# analogTCO-RJ-alone.net
KiCad netlist of a schematic drawn in EAGLE
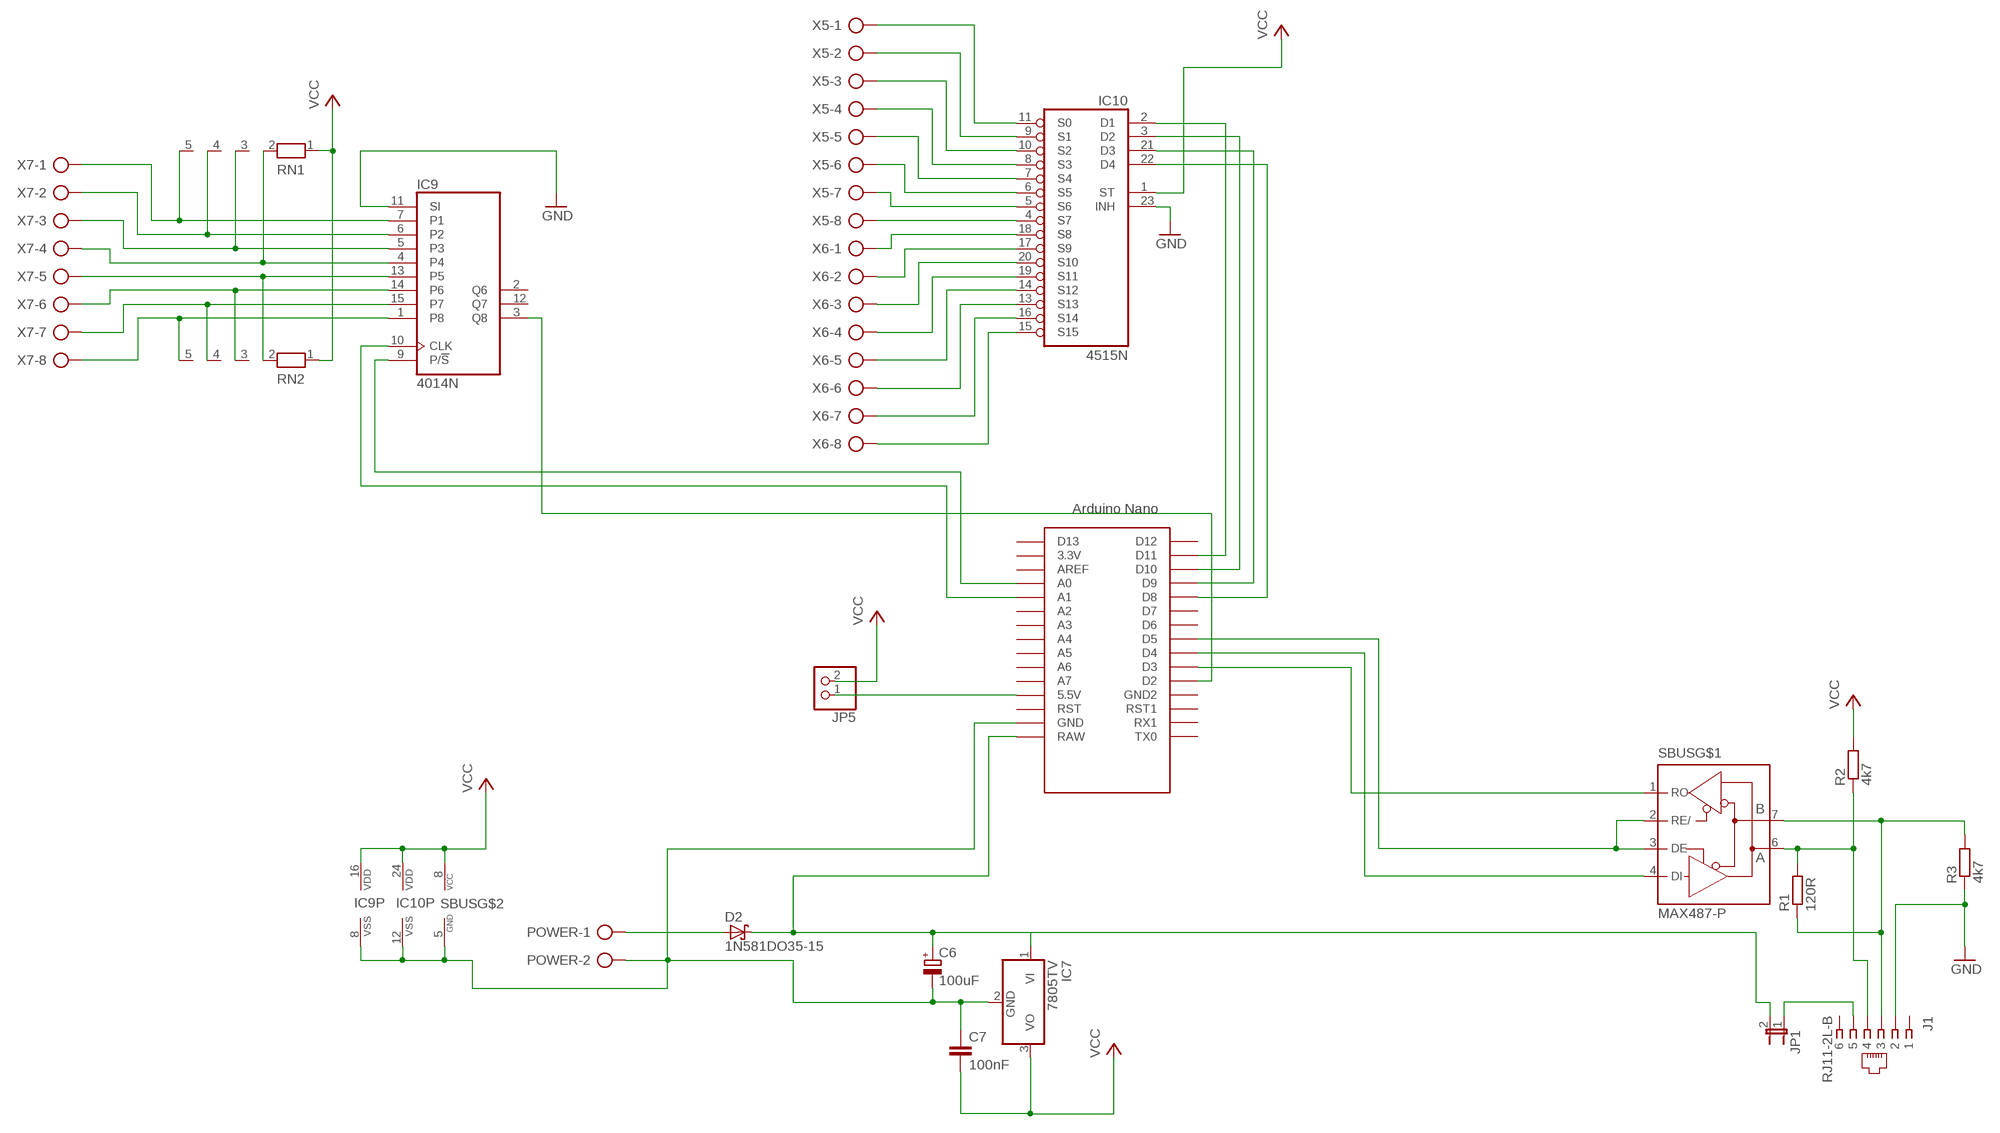
[diagram p0: schematic, sheet 1]

(export (version "E")
  (design (tool "Eeschema 10.0.6"))
  (components
    (comp (ref "C6")
      (value "100uF")
      (footprint "eagle-import:E2,5-6")
      (libsource (lib "eagle-import") (part "CPOL-EUE2.5-6"))
    )
    (comp (ref "C7")
      (value "100nF")
      (footprint "eagle-import:C025-025X050")
      (libsource (lib "eagle-import") (part "C-EU025-025X050"))
    )
    (comp (ref "D2")
      (value "1N581DO35-15")
      (footprint "eagle-import:DO35-10")
      (libsource (lib "eagle-import") (part "1N581DO35-15"))
    )
    (comp (ref "IC7")
      (value "7805TV")
      (footprint "eagle-import:TO220V")
      (libsource (lib "eagle-import") (part "78TV05"))
    )
    (comp (ref "IC9")
      (value "4014N")
      (footprint "eagle-import:DIL16")
      (libsource (lib "eagle-import") (part "4014N"))
    )
    (comp (ref "IC10")
      (value "4515N")
      (footprint "eagle-import:DIL24-6")
      (libsource (lib "eagle-import") (part "4515N"))
    )
    (comp (ref "J1")
      (value "RJ11-2L-B")
      (footprint "eagle-import:RJ11-NO_SHIELD")
      (fields (field (name "MF") "TYCO ELECTRONICS"))
      (libsource (lib "eagle-import") (part "RJ11-2L-B"))
    )
    (comp (ref "JP1")
      (value "JP1E")
      (footprint "eagle-import:JP1")
      (libsource (lib "eagle-import") (part "JP1E"))
    )
    (comp (ref "JP5")
      (value "PINHD-1X2")
      (footprint "eagle-import:1X02")
      (libsource (lib "eagle-import") (part "PINHD-1X2"))
    )
    (comp (ref "POWER")
      (value "AK500/2")
      (footprint "eagle-import:AK500_2")
      (libsource (lib "eagle-import") (part "AK500/2"))
    )
    (comp (ref "R1")
      (value "120R")
      (footprint "eagle-import:0207_12")
      (libsource (lib "eagle-import") (part "R-EU_0207/12"))
    )
    (comp (ref "R2")
      (value "4k7")
      (footprint "eagle-import:0207_12")
      (libsource (lib "eagle-import") (part "R-EU_0207/12"))
    )
    (comp (ref "R3")
      (value "4k7")
      (footprint "eagle-import:0207_12")
      (libsource (lib "eagle-import") (part "R-EU_0207/12"))
    )
    (comp (ref "RN1")
      (value "RN04")
      (footprint "eagle-import:RN-5")
      (libsource (lib "eagle-import") (part "RN04"))
    )
    (comp (ref "RN2")
      (value "RN04")
      (footprint "eagle-import:RN-5")
      (libsource (lib "eagle-import") (part "RN04"))
    )
    (comp (ref "SBUS")
      (value "MAX487-P")
      (footprint "eagle-import:DIL08")
      (libsource (lib "eagle-import") (part "MAX487-P"))
    )
    (comp (ref "U$1")
      (value "NANO")
      (footprint "eagle-import:NANO")
      (libsource (lib "eagle-import") (part "NANO"))
    )
    (comp (ref "X5")
      (value "AK500/8")
      (footprint "eagle-import:AK500_8")
      (libsource (lib "eagle-import") (part "AK500/8"))
    )
    (comp (ref "X6")
      (value "AK500/8")
      (footprint "eagle-import:AK500_8")
      (libsource (lib "eagle-import") (part "AK500/8"))
    )
    (comp (ref "X7")
      (value "AK500/8")
      (footprint "eagle-import:AK500_8")
      (libsource (lib "eagle-import") (part "AK500/8"))
    )
  )
  (nets
    (net (code "1") (name "GND") (class "Default")
      (node (ref "C6") (pin "-") (pinfunction "-_-") (pintype "passive"))
      (node (ref "C7") (pin "1") (pinfunction "1_1") (pintype "passive"))
      (node (ref "IC10") (pin "12") (pinfunction "VSS_12") (pintype "power_in"))
      (node (ref "IC10") (pin "23") (pinfunction "INH_23") (pintype "input"))
      (node (ref "IC7") (pin "2") (pinfunction "GND_2") (pintype "passive"))
      (node (ref "IC9") (pin "11") (pinfunction "SI_11") (pintype "input"))
      (node (ref "IC9") (pin "8") (pinfunction "VSS_8") (pintype "power_in"))
      (node (ref "J1") (pin "2") (pinfunction "2_2") (pintype "passive"))
      (node (ref "POWER") (pin "2") (pinfunction "KL_2") (pintype "passive"))
      (node (ref "R3") (pin "1") (pinfunction "1_1") (pintype "passive"))
      (node (ref "SBUS") (pin "5") (pinfunction "GND_5") (pintype "power_in"))
      (node (ref "U$1") (pin "GND") (pinfunction "GND_GND") (pintype "bidirectional"))
    )
    (net (code "2") (name "Net-(IC7-VI)") (class "Default")
      (node (ref "C6") (pin "+") (pinfunction "+_+") (pintype "passive"))
      (node (ref "D2") (pin "C") (pinfunction "C_C") (pintype "passive"))
      (node (ref "IC7") (pin "1") (pinfunction "VI_1") (pintype "input"))
      (node (ref "JP1") (pin "2") (pinfunction "2_2") (pintype "passive"))
      (node (ref "U$1") (pin "RAW") (pinfunction "RAW_RAW") (pintype "bidirectional"))
    )
    (net (code "3") (name "Net-(IC9A-CLK)") (class "Default")
      (node (ref "IC9") (pin "10") (pinfunction "CLK_10") (pintype "input"))
      (node (ref "U$1") (pin "A1") (pinfunction "A1_A1") (pintype "bidirectional"))
    )
    (net (code "4") (name "Net-(IC9A-P1)") (class "Default")
      (node (ref "IC9") (pin "7") (pinfunction "P1_7") (pintype "input"))
      (node (ref "RN1") (pin "5") (pinfunction "5_5") (pintype "passive"))
      (node (ref "X7") (pin "1") (pinfunction "KL_1") (pintype "passive"))
    )
    (net (code "5") (name "Net-(IC9A-P2)") (class "Default")
      (node (ref "IC9") (pin "6") (pinfunction "P2_6") (pintype "input"))
      (node (ref "RN1") (pin "4") (pinfunction "4_4") (pintype "passive"))
      (node (ref "X7") (pin "2") (pinfunction "KL_2") (pintype "passive"))
    )
    (net (code "6") (name "Net-(IC9A-P3)") (class "Default")
      (node (ref "IC9") (pin "5") (pinfunction "P3_5") (pintype "input"))
      (node (ref "RN1") (pin "3") (pinfunction "3_3") (pintype "passive"))
      (node (ref "X7") (pin "3") (pinfunction "KL_3") (pintype "passive"))
    )
    (net (code "7") (name "Net-(IC9A-P4)") (class "Default")
      (node (ref "IC9") (pin "4") (pinfunction "P4_4") (pintype "input"))
      (node (ref "RN1") (pin "2") (pinfunction "2_2") (pintype "passive"))
      (node (ref "X7") (pin "4") (pinfunction "KL_4") (pintype "passive"))
    )
    (net (code "8") (name "Net-(IC9A-P5)") (class "Default")
      (node (ref "IC9") (pin "13") (pinfunction "P5_13") (pintype "input"))
      (node (ref "RN2") (pin "2") (pinfunction "2_2") (pintype "passive"))
      (node (ref "X7") (pin "5") (pinfunction "KL_5") (pintype "passive"))
    )
    (net (code "9") (name "Net-(IC9A-P6)") (class "Default")
      (node (ref "IC9") (pin "14") (pinfunction "P6_14") (pintype "input"))
      (node (ref "RN2") (pin "3") (pinfunction "3_3") (pintype "passive"))
      (node (ref "X7") (pin "6") (pinfunction "KL_6") (pintype "passive"))
    )
    (net (code "10") (name "Net-(IC9A-P7)") (class "Default")
      (node (ref "IC9") (pin "15") (pinfunction "P7_15") (pintype "input"))
      (node (ref "RN2") (pin "4") (pinfunction "4_4") (pintype "passive"))
      (node (ref "X7") (pin "7") (pinfunction "KL_7") (pintype "passive"))
    )
    (net (code "11") (name "Net-(IC9A-P8)") (class "Default")
      (node (ref "IC9") (pin "1") (pinfunction "P8_1") (pintype "input"))
      (node (ref "RN2") (pin "5") (pinfunction "5_5") (pintype "passive"))
      (node (ref "X7") (pin "8") (pinfunction "KL_8") (pintype "passive"))
    )
    (net (code "12") (name "Net-(IC9A-P{slash}~{S})") (class "Default")
      (node (ref "IC9") (pin "9") (pinfunction "P/~{S}_9") (pintype "input"))
      (node (ref "U$1") (pin "A0") (pinfunction "A0_A0") (pintype "bidirectional"))
    )
    (net (code "13") (name "Net-(IC9A-Q8)") (class "Default")
      (node (ref "IC9") (pin "3") (pinfunction "Q8_3") (pintype "output"))
      (node (ref "U$1") (pin "D2") (pinfunction "D2_D2") (pintype "bidirectional"))
    )
    (net (code "14") (name "Net-(IC10A-D1)") (class "Default")
      (node (ref "IC10") (pin "2") (pinfunction "D1_2") (pintype "input"))
      (node (ref "U$1") (pin "D11") (pinfunction "D11_D11") (pintype "bidirectional"))
    )
    (net (code "15") (name "Net-(IC10A-D2)") (class "Default")
      (node (ref "IC10") (pin "3") (pinfunction "D2_3") (pintype "input"))
      (node (ref "U$1") (pin "D10") (pinfunction "D10_D10") (pintype "bidirectional"))
    )
    (net (code "16") (name "Net-(IC10A-D3)") (class "Default")
      (node (ref "IC10") (pin "21") (pinfunction "D3_21") (pintype "input"))
      (node (ref "U$1") (pin "D9") (pinfunction "D9_D9") (pintype "bidirectional"))
    )
    (net (code "17") (name "Net-(IC10A-D4)") (class "Default")
      (node (ref "IC10") (pin "22") (pinfunction "D4_22") (pintype "input"))
      (node (ref "U$1") (pin "D8") (pinfunction "D8_D8") (pintype "bidirectional"))
    )
    (net (code "18") (name "Net-(IC10A-S0)") (class "Default")
      (node (ref "IC10") (pin "11") (pinfunction "S0_11") (pintype "output"))
      (node (ref "X5") (pin "1") (pinfunction "KL_1") (pintype "passive"))
    )
    (net (code "19") (name "Net-(IC10A-S1)") (class "Default")
      (node (ref "IC10") (pin "9") (pinfunction "S1_9") (pintype "output"))
      (node (ref "X5") (pin "2") (pinfunction "KL_2") (pintype "passive"))
    )
    (net (code "20") (name "Net-(IC10A-S2)") (class "Default")
      (node (ref "IC10") (pin "10") (pinfunction "S2_10") (pintype "output"))
      (node (ref "X5") (pin "3") (pinfunction "KL_3") (pintype "passive"))
    )
    (net (code "21") (name "Net-(IC10A-S3)") (class "Default")
      (node (ref "IC10") (pin "8") (pinfunction "S3_8") (pintype "output"))
      (node (ref "X5") (pin "4") (pinfunction "KL_4") (pintype "passive"))
    )
    (net (code "22") (name "Net-(IC10A-S4)") (class "Default")
      (node (ref "IC10") (pin "7") (pinfunction "S4_7") (pintype "output"))
      (node (ref "X5") (pin "5") (pinfunction "KL_5") (pintype "passive"))
    )
    (net (code "23") (name "Net-(IC10A-S5)") (class "Default")
      (node (ref "IC10") (pin "6") (pinfunction "S5_6") (pintype "output"))
      (node (ref "X5") (pin "6") (pinfunction "KL_6") (pintype "passive"))
    )
    (net (code "24") (name "Net-(IC10A-S6)") (class "Default")
      (node (ref "IC10") (pin "5") (pinfunction "S6_5") (pintype "output"))
      (node (ref "X5") (pin "7") (pinfunction "KL_7") (pintype "passive"))
    )
    (net (code "25") (name "Net-(IC10A-S7)") (class "Default")
      (node (ref "IC10") (pin "4") (pinfunction "S7_4") (pintype "output"))
      (node (ref "X5") (pin "8") (pinfunction "KL_8") (pintype "passive"))
    )
    (net (code "26") (name "Net-(IC10A-S8)") (class "Default")
      (node (ref "IC10") (pin "18") (pinfunction "S8_18") (pintype "output"))
      (node (ref "X6") (pin "1") (pinfunction "KL_1") (pintype "passive"))
    )
    (net (code "27") (name "Net-(IC10A-S9)") (class "Default")
      (node (ref "IC10") (pin "17") (pinfunction "S9_17") (pintype "output"))
      (node (ref "X6") (pin "2") (pinfunction "KL_2") (pintype "passive"))
    )
    (net (code "28") (name "Net-(IC10A-S10)") (class "Default")
      (node (ref "IC10") (pin "20") (pinfunction "S10_20") (pintype "output"))
      (node (ref "X6") (pin "3") (pinfunction "KL_3") (pintype "passive"))
    )
    (net (code "29") (name "Net-(IC10A-S11)") (class "Default")
      (node (ref "IC10") (pin "19") (pinfunction "S11_19") (pintype "output"))
      (node (ref "X6") (pin "4") (pinfunction "KL_4") (pintype "passive"))
    )
    (net (code "30") (name "Net-(IC10A-S12)") (class "Default")
      (node (ref "IC10") (pin "14") (pinfunction "S12_14") (pintype "output"))
      (node (ref "X6") (pin "5") (pinfunction "KL_5") (pintype "passive"))
    )
    (net (code "31") (name "Net-(IC10A-S13)") (class "Default")
      (node (ref "IC10") (pin "13") (pinfunction "S13_13") (pintype "output"))
      (node (ref "X6") (pin "6") (pinfunction "KL_6") (pintype "passive"))
    )
    (net (code "32") (name "Net-(IC10A-S14)") (class "Default")
      (node (ref "IC10") (pin "16") (pinfunction "S14_16") (pintype "output"))
      (node (ref "X6") (pin "7") (pinfunction "KL_7") (pintype "passive"))
    )
    (net (code "33") (name "Net-(IC10A-S15)") (class "Default")
      (node (ref "IC10") (pin "15") (pinfunction "S15_15") (pintype "output"))
      (node (ref "X6") (pin "8") (pinfunction "KL_8") (pintype "passive"))
    )
    (net (code "34") (name "Net-(J1-Pad5)") (class "Default")
      (node (ref "J1") (pin "5") (pinfunction "5_5") (pintype "passive"))
      (node (ref "JP1") (pin "1") (pinfunction "1_1") (pintype "passive"))
    )
    (net (code "35") (name "Net-(POWERA-KL)") (class "Default")
      (node (ref "D2") (pin "A") (pinfunction "A_A") (pintype "passive"))
      (node (ref "POWER") (pin "1") (pinfunction "KL_1") (pintype "passive"))
    )
    (net (code "36") (name "Net-(SBUSA-A)") (class "Default")
      (node (ref "J1") (pin "4") (pinfunction "4_4") (pintype "passive"))
      (node (ref "R1") (pin "2") (pinfunction "2_2") (pintype "passive"))
      (node (ref "R2") (pin "1") (pinfunction "1_1") (pintype "passive"))
      (node (ref "SBUS") (pin "6") (pinfunction "A_6") (pintype "passive"))
    )
    (net (code "37") (name "Net-(SBUSA-B)") (class "Default")
      (node (ref "J1") (pin "3") (pinfunction "3_3") (pintype "passive"))
      (node (ref "R1") (pin "1") (pinfunction "1_1") (pintype "passive"))
      (node (ref "R3") (pin "2") (pinfunction "2_2") (pintype "passive"))
      (node (ref "SBUS") (pin "7") (pinfunction "B_7") (pintype "passive"))
    )
    (net (code "38") (name "Net-(SBUSA-DE)") (class "Default")
      (node (ref "SBUS") (pin "2") (pinfunction "RE/_2") (pintype "input"))
      (node (ref "SBUS") (pin "3") (pinfunction "DE_3") (pintype "input"))
      (node (ref "U$1") (pin "D5") (pinfunction "D5_D5") (pintype "bidirectional"))
    )
    (net (code "39") (name "Net-(SBUSA-DI)") (class "Default")
      (node (ref "SBUS") (pin "4") (pinfunction "DI_4") (pintype "input"))
      (node (ref "U$1") (pin "D4") (pinfunction "D4_D4") (pintype "bidirectional"))
    )
    (net (code "40") (name "Net-(SBUSA-RO)") (class "Default")
      (node (ref "SBUS") (pin "1") (pinfunction "RO_1") (pintype "output"))
      (node (ref "U$1") (pin "D3") (pinfunction "D3_D3") (pintype "bidirectional"))
    )
    (net (code "41") (name "Net-(U$1-5.5V)") (class "Default")
      (node (ref "JP5") (pin "1") (pinfunction "1_1") (pintype "passive"))
      (node (ref "U$1") (pin "5V") (pinfunction "5.5V_5V") (pintype "bidirectional"))
    )
    (net (code "42") (name "VCC") (class "Default")
      (node (ref "C7") (pin "2") (pinfunction "2_2") (pintype "passive"))
      (node (ref "IC10") (pin "1") (pinfunction "ST_1") (pintype "input"))
      (node (ref "IC10") (pin "24") (pinfunction "VDD_24") (pintype "power_in"))
      (node (ref "IC7") (pin "3") (pinfunction "VO_3") (pintype "passive"))
      (node (ref "IC9") (pin "16") (pinfunction "VDD_16") (pintype "power_in"))
      (node (ref "JP5") (pin "2") (pinfunction "2_2") (pintype "passive"))
      (node (ref "R2") (pin "2") (pinfunction "2_2") (pintype "passive"))
      (node (ref "RN1") (pin "1") (pinfunction "1_1") (pintype "passive"))
      (node (ref "RN2") (pin "1") (pinfunction "1_1") (pintype "passive"))
      (node (ref "SBUS") (pin "8") (pinfunction "VCC_8") (pintype "power_in"))
    )
    (net (code "43") (name "unconnected-(IC9A-Q6-Pad2)") (class "Default")
      (node (ref "IC9") (pin "2") (pinfunction "Q6_2") (pintype "output"))
    )
    (net (code "44") (name "unconnected-(IC9A-Q7-Pad12)") (class "Default")
      (node (ref "IC9") (pin "12") (pinfunction "Q7_12") (pintype "output"))
    )
    (net (code "45") (name "unconnected-(J1-Pad1)") (class "Default")
      (node (ref "J1") (pin "1") (pinfunction "1_1") (pintype "passive"))
    )
    (net (code "46") (name "unconnected-(J1-Pad6)") (class "Default")
      (node (ref "J1") (pin "6") (pinfunction "6_6") (pintype "passive"))
    )
    (net (code "47") (name "unconnected-(U$1-GND2-PadGND1)") (class "Default")
      (node (ref "U$1") (pin "GND1") (pinfunction "GND2_GND1") (pintype "bidirectional"))
    )
    (net (code "48") (name "unconnected-(U$1-Pad3.3V)") (class "Default")
      (node (ref "U$1") (pin "3.3V") (pinfunction "3.3V_3.3V") (pintype "bidirectional"))
    )
    (net (code "49") (name "unconnected-(U$1-PadA2)") (class "Default")
      (node (ref "U$1") (pin "A2") (pinfunction "A2_A2") (pintype "bidirectional"))
    )
    (net (code "50") (name "unconnected-(U$1-PadA3)") (class "Default")
      (node (ref "U$1") (pin "A3") (pinfunction "A3_A3") (pintype "bidirectional"))
    )
    (net (code "51") (name "unconnected-(U$1-PadA4)") (class "Default")
      (node (ref "U$1") (pin "A4") (pinfunction "A4_A4") (pintype "bidirectional"))
    )
    (net (code "52") (name "unconnected-(U$1-PadA5)") (class "Default")
      (node (ref "U$1") (pin "A5") (pinfunction "A5_A5") (pintype "bidirectional"))
    )
    (net (code "53") (name "unconnected-(U$1-PadA6)") (class "Default")
      (node (ref "U$1") (pin "A6") (pinfunction "A6_A6") (pintype "bidirectional"))
    )
    (net (code "54") (name "unconnected-(U$1-PadA7)") (class "Default")
      (node (ref "U$1") (pin "A7") (pinfunction "A7_A7") (pintype "bidirectional"))
    )
    (net (code "55") (name "unconnected-(U$1-PadAREF)") (class "Default")
      (node (ref "U$1") (pin "AREF") (pinfunction "AREF_AREF") (pintype "bidirectional"))
    )
    (net (code "56") (name "unconnected-(U$1-PadD6)") (class "Default")
      (node (ref "U$1") (pin "D6") (pinfunction "D6_D6") (pintype "bidirectional"))
    )
    (net (code "57") (name "unconnected-(U$1-PadD7)") (class "Default")
      (node (ref "U$1") (pin "D7") (pinfunction "D7_D7") (pintype "bidirectional"))
    )
    (net (code "58") (name "unconnected-(U$1-PadD12)") (class "Default")
      (node (ref "U$1") (pin "D12") (pinfunction "D12_D12") (pintype "bidirectional"))
    )
    (net (code "59") (name "unconnected-(U$1-PadD13)") (class "Default")
      (node (ref "U$1") (pin "D13") (pinfunction "D13_D13") (pintype "bidirectional"))
    )
    (net (code "60") (name "unconnected-(U$1-PadICSP1)") (class "Default")
      (node (ref "U$1") (pin "ICSP1") (pinfunction "ICSP1_ICSP1") (pintype "bidirectional"))
    )
    (net (code "61") (name "unconnected-(U$1-PadICSP2)") (class "Default")
      (node (ref "U$1") (pin "ICSP2") (pinfunction "ICSP2_ICSP2") (pintype "bidirectional"))
    )
    (net (code "62") (name "unconnected-(U$1-PadICSP3)") (class "Default")
      (node (ref "U$1") (pin "ICSP3") (pinfunction "ICSP3_ICSP3") (pintype "bidirectional"))
    )
    (net (code "63") (name "unconnected-(U$1-PadICSP4)") (class "Default")
      (node (ref "U$1") (pin "ICSP4") (pinfunction "ICSP4_ICSP4") (pintype "bidirectional"))
    )
    (net (code "64") (name "unconnected-(U$1-PadICSP5)") (class "Default")
      (node (ref "U$1") (pin "ICSP5") (pinfunction "ICSP5_ICSP5") (pintype "bidirectional"))
    )
    (net (code "65") (name "unconnected-(U$1-PadICSP6)") (class "Default")
      (node (ref "U$1") (pin "ICSP6") (pinfunction "ICSP6_ICSP6") (pintype "bidirectional"))
    )
    (net (code "66") (name "unconnected-(U$1-PadRST)") (class "Default")
      (node (ref "U$1") (pin "RST") (pinfunction "RST_RST") (pintype "bidirectional"))
    )
    (net (code "67") (name "unconnected-(U$1-PadRST1)") (class "Default")
      (node (ref "U$1") (pin "RST1") (pinfunction "RST1_RST1") (pintype "bidirectional"))
    )
    (net (code "68") (name "unconnected-(U$1-PadRX1)") (class "Default")
      (node (ref "U$1") (pin "RX1") (pinfunction "RX1_RX1") (pintype "bidirectional"))
    )
    (net (code "69") (name "unconnected-(U$1-PadTX0)") (class "Default")
      (node (ref "U$1") (pin "TX0") (pinfunction "TX0_TX0") (pintype "bidirectional"))
    )
  )
)
